# eps_flash.net
KiCad netlist of a schematic drawn in Altium Designer
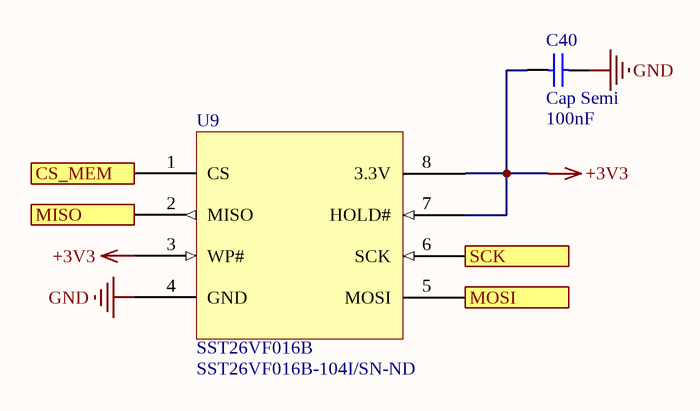
[diagram p0: eps_flash.SchDoc]

(export (version "E")
  (design (tool "Eeschema 10.0.6"))
  (components
    (comp (ref "C40")
      (value "Cap Semi")
      (footprint "1608[0603]")
      (description "Capacitor (Semiconductor SIM Model)")
      (fields (field (name "ALTIUM_VALUE") "100nF") (field (name "PUBLISHER") "Altium Limited"))
      (libsource (lib "Miscellaneous Devices") (part "Cap Semi"))
    )
    (comp (ref "U9")
      (value "SST26VF016B")
      (footprint "SOIC127P500X600-8N")
      (description "2.5V/3.0V 16 Mbit Serial Quad I/O (SQI) Flash Memory")
      (fields (field (name "SUPPLIER PART NUMBER 1") "SST26VF016B-104I/SN-ND"))
      (libsource (lib "heron-general") (part "SST26VF016B"))
    )
  )
  (nets
    (net (code "1") (name "+3V3") (class "Default")
      (node (ref "C40") (pin "1") (pinfunction "1_1") (pintype "passive"))
      (node (ref "U9") (pin "3") (pinfunction "WP#_3") (pintype "input"))
      (node (ref "U9") (pin "7") (pinfunction "HOLD#_7") (pintype "input"))
      (node (ref "U9") (pin "8") (pinfunction "3.3V_8") (pintype "power_in"))
    )
    (net (code "2") (name "/CS_MEM") (class "Default")
      (node (ref "U9") (pin "1") (pinfunction "CS_1") (pintype "passive"))
    )
    (net (code "3") (name "/MISO") (class "Default")
      (node (ref "U9") (pin "2") (pinfunction "MISO_2") (pintype "output"))
    )
    (net (code "4") (name "/MOSI") (class "Default")
      (node (ref "U9") (pin "5") (pinfunction "MOSI_5") (pintype "passive"))
    )
    (net (code "5") (name "/SCK") (class "Default")
      (node (ref "U9") (pin "6") (pinfunction "SCK_6") (pintype "input"))
    )
    (net (code "6") (name "GND") (class "Default")
      (node (ref "C40") (pin "2") (pinfunction "2_2") (pintype "passive"))
      (node (ref "U9") (pin "4") (pinfunction "GND_4") (pintype "power_in"))
    )
  )
)
